# 04-POWERV2_1.net
KiCad netlist of a schematic drawn in Altium Designer
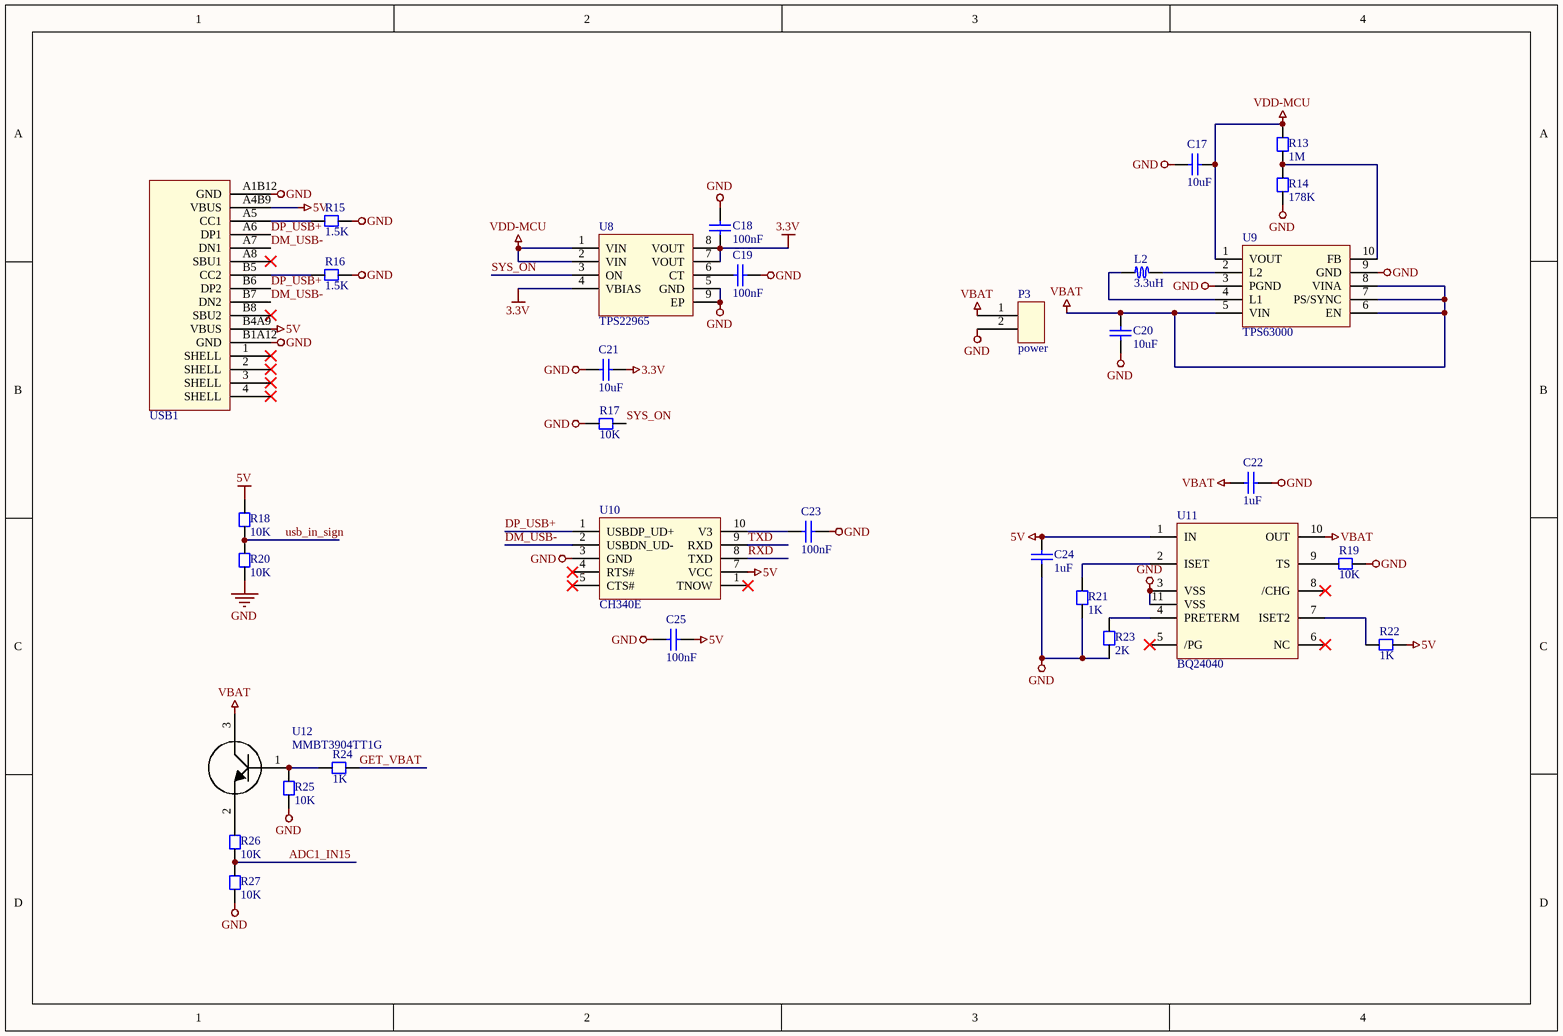
[diagram p0: 04-POWERV2.1.SchDoc]

(export (version "E")
  (design (tool "Eeschema 10.0.6"))
  (components
    (comp (ref "C17")
      (value "10uF")
      (footprint "CC1005-0402")
      (description "贴片电容")
      (libsource (lib "tianxiaohua_Schlib") (part "Chip capacitor"))
    )
    (comp (ref "C18")
      (value "100nF")
      (footprint "CC1005-0402")
      (description "贴片电容")
      (libsource (lib "tianxiaohua_Schlib") (part "Chip capacitor"))
    )
    (comp (ref "C19")
      (value "100nF")
      (footprint "CC1005-0402")
      (description "贴片电容")
      (libsource (lib "tianxiaohua_Schlib") (part "Chip capacitor"))
    )
    (comp (ref "C20")
      (value "10uF")
      (footprint "CC1005-0402")
      (description "贴片电容")
      (libsource (lib "tianxiaohua_Schlib") (part "Chip capacitor"))
    )
    (comp (ref "C21")
      (value "10uF")
      (footprint "CC1005-0402")
      (description "贴片电容")
      (libsource (lib "tianxiaohua_Schlib") (part "Chip capacitor"))
    )
    (comp (ref "C22")
      (value "1uF")
      (footprint "CC1005-0402")
      (description "贴片电容")
      (libsource (lib "tianxiaohua_Schlib") (part "Chip capacitor"))
    )
    (comp (ref "C23")
      (value "100nF")
      (footprint "CC1005-0402")
      (description "贴片电容")
      (libsource (lib "tianxiaohua_Schlib") (part "Chip capacitor"))
    )
    (comp (ref "C24")
      (value "1uF")
      (footprint "CC1005-0402")
      (description "贴片电容")
      (libsource (lib "tianxiaohua_Schlib") (part "Chip capacitor"))
    )
    (comp (ref "C25")
      (value "100nF")
      (footprint "CC1005-0402")
      (description "贴片电容")
      (libsource (lib "tianxiaohua_Schlib") (part "Chip capacitor"))
    )
    (comp (ref "L2")
      (value "3.3uH")
      (footprint "Inductor-0805")
      (description "贴片电感")
      (libsource (lib "tianxiaohua_Schlib") (part "Chip inductor"))
    )
    (comp (ref "P3")
      (value "power")
      (footprint "POWER-3.7V")
      (libsource (lib "tianxiaohua_Schlib") (part "power"))
    )
    (comp (ref "R13")
      (value "1M")
      (footprint "CR1005-0402")
      (description "贴片电阻")
      (libsource (lib "") (part "Chip resistor_1"))
    )
    (comp (ref "R14")
      (value "178K")
      (footprint "CR1005-0402")
      (description "贴片电阻")
      (libsource (lib "") (part "Chip resistor_3"))
    )
    (comp (ref "R15")
      (value "1.5K")
      (footprint "CR1005-0402")
      (description "贴片电阻")
      (libsource (lib "") (part "Chip resistor_2"))
    )
    (comp (ref "R16")
      (value "1.5K")
      (footprint "CR1005-0402")
      (description "贴片电阻")
      (libsource (lib "") (part "Chip resistor_2"))
    )
    (comp (ref "R17")
      (value "10K")
      (footprint "CR1005-0402")
      (description "贴片电阻")
      (libsource (lib "") (part "Chip resistor_2"))
    )
    (comp (ref "R18")
      (value "10K")
      (footprint "CR1005-0402")
      (description "贴片电阻")
      (libsource (lib "") (part "Chip resistor_1"))
    )
    (comp (ref "R19")
      (value "10K")
      (footprint "CR1005-0402")
      (description "贴片电阻")
      (libsource (lib "tianxiaohua_Schlib") (part "Chip resistor"))
    )
    (comp (ref "R20")
      (value "10K")
      (footprint "CR1005-0402")
      (description "贴片电阻")
      (libsource (lib "") (part "Chip resistor_1"))
    )
    (comp (ref "R21")
      (value "1K")
      (footprint "CR1005-0402")
      (description "贴片电阻")
      (libsource (lib "") (part "Chip resistor_1"))
    )
    (comp (ref "R22")
      (value "1K")
      (footprint "CR1005-0402")
      (description "贴片电阻")
      (libsource (lib "tianxiaohua_Schlib") (part "Chip resistor"))
    )
    (comp (ref "R23")
      (value "2K")
      (footprint "CR1005-0402")
      (description "贴片电阻")
      (libsource (lib "") (part "Chip resistor_1"))
    )
    (comp (ref "R24")
      (value "1K")
      (footprint "CR1005-0402")
      (description "贴片电阻")
      (libsource (lib "tianxiaohua_Schlib") (part "Chip resistor"))
    )
    (comp (ref "R25")
      (value "10K")
      (footprint "CR1005-0402")
      (description "贴片电阻")
      (libsource (lib "") (part "Chip resistor_1"))
    )
    (comp (ref "R26")
      (value "10K")
      (footprint "CR1005-0402")
      (description "贴片电阻")
      (libsource (lib "") (part "Chip resistor_1"))
    )
    (comp (ref "R27")
      (value "10K")
      (footprint "CR1005-0402")
      (description "贴片电阻")
      (libsource (lib "") (part "Chip resistor_1"))
    )
    (comp (ref "U8")
      (value "TPS22965")
      (footprint "UDFN-8")
      (description "DFN-8 功率开关芯片 TPS22965DSGR")
      (libsource (lib "tianxiaohua_Schlib") (part "TPS22965"))
    )
    (comp (ref "U9")
      (value "TPS63000")
      (footprint "SON10")
      (description "宽电压电源转换芯片输出3.3V输入1V至6V")
      (libsource (lib "tianxiaohua_Schlib") (part "TPS63000"))
    )
    (comp (ref "U10")
      (value "CH340E")
      (footprint "MSOP-10")
      (description "usd转串口芯片 MSOP10封装")
      (libsource (lib "tianxiaohua_Schlib") (part "CH340E"))
    )
    (comp (ref "U11")
      (value "BQ24040")
      (footprint "WSON-10_L2.0-W2.0-P0.40-BL-EP")
      (description "1A 具有自动启动功能的单输入，单节锂离子和锂聚合物电池充电\r\n器")
      (libsource (lib "tianxiaohua_Schlib") (part "BQ24041"))
    )
    (comp (ref "U12")
      (value "MMBT3904TT1G")
      (footprint "SOT-416")
      (description "NPN 电流 - 集电极（Ic）（最大值）：200mA 电压 - 集射极击穿（最大值）：40V SOT-23-3")
      (libsource (lib "tianxiaohua_Schlib") (part "MMBT3904TT1G"))
    )
    (comp (ref "USB1")
      (value "Tpye-c 16P")
      (footprint "TYPE-C 16P")
      (description "16P 封装的TYPE -c接口 4固定插脚 双向")
      (libsource (lib "tianxiaohua_Schlib") (part "Tpye-c 16P"))
    )
  )
  (nets
    (net (code "1") (name "/ADC1_IN15") (class "Default")
      (node (ref "R26") (pin "2") (pinfunction "2_2") (pintype "passive"))
      (node (ref "R27") (pin "1") (pinfunction "1_1") (pintype "passive"))
    )
    (net (code "2") (name "/DM_USB-") (class "Default")
      (node (ref "U10") (pin "2") (pinfunction "USBDN_UD-_2") (pintype "passive"))
      (node (ref "USB1") (pin "A7") (pinfunction "DN1_A7") (pintype "power_in"))
      (node (ref "USB1") (pin "B7") (pinfunction "DN2_B7") (pintype "power_in"))
    )
    (net (code "3") (name "/DP_USB+") (class "Default")
      (node (ref "U10") (pin "1") (pinfunction "USBDP_UD+_1") (pintype "passive"))
      (node (ref "USB1") (pin "A6") (pinfunction "DP1_A6") (pintype "power_in"))
      (node (ref "USB1") (pin "B6") (pinfunction "DP2_B6") (pintype "power_in"))
    )
    (net (code "4") (name "/GET_VBAT") (class "Default")
      (node (ref "R24") (pin "2") (pinfunction "2_2") (pintype "passive"))
    )
    (net (code "5") (name "/RXD") (class "Default")
      (node (ref "U10") (pin "8") (pinfunction "TXD_8") (pintype "passive"))
    )
    (net (code "6") (name "/SYS_ON") (class "Default")
      (node (ref "R17") (pin "1") (pinfunction "1_1") (pintype "passive"))
      (node (ref "U8") (pin "3") (pinfunction "ON_3") (pintype "passive"))
    )
    (net (code "7") (name "/TXD") (class "Default")
      (node (ref "U10") (pin "9") (pinfunction "RXD_9") (pintype "passive"))
    )
    (net (code "8") (name "/usb_in_sign") (class "Default")
      (node (ref "R18") (pin "2") (pinfunction "2_2") (pintype "passive"))
      (node (ref "R20") (pin "1") (pinfunction "1_1") (pintype "passive"))
    )
    (net (code "9") (name "3.3V") (class "Default")
      (node (ref "C18") (pin "1") (pinfunction "1_1") (pintype "passive"))
      (node (ref "C21") (pin "2") (pinfunction "2_2") (pintype "passive"))
      (node (ref "U8") (pin "4") (pinfunction "VBIAS_4") (pintype "passive"))
      (node (ref "U8") (pin "7") (pinfunction "VOUT_7") (pintype "passive"))
      (node (ref "U8") (pin "8") (pinfunction "VOUT_8") (pintype "passive"))
    )
    (net (code "10") (name "5V") (class "Default")
      (node (ref "C24") (pin "1") (pinfunction "1_1") (pintype "passive"))
      (node (ref "C25") (pin "2") (pinfunction "2_2") (pintype "passive"))
      (node (ref "R18") (pin "1") (pinfunction "1_1") (pintype "passive"))
      (node (ref "R22") (pin "2") (pinfunction "2_2") (pintype "passive"))
      (node (ref "U10") (pin "7") (pinfunction "VCC_7") (pintype "passive"))
      (node (ref "U11") (pin "1") (pinfunction "IN_1") (pintype "passive"))
      (node (ref "USB1") (pin "A4B9") (pinfunction "VBUS_A4B9") (pintype "power_in"))
      (node (ref "USB1") (pin "B4A9") (pinfunction "VBUS_B4A9") (pintype "power_in"))
    )
    (net (code "11") (name "GND") (class "Default")
      (node (ref "C17") (pin "1") (pinfunction "1_1") (pintype "passive"))
      (node (ref "C18") (pin "2") (pinfunction "2_2") (pintype "passive"))
      (node (ref "C19") (pin "1") (pinfunction "1_1") (pintype "passive"))
      (node (ref "C20") (pin "1") (pinfunction "1_1") (pintype "passive"))
      (node (ref "C21") (pin "1") (pinfunction "1_1") (pintype "passive"))
      (node (ref "C22") (pin "1") (pinfunction "1_1") (pintype "passive"))
      (node (ref "C23") (pin "2") (pinfunction "2_2") (pintype "passive"))
      (node (ref "C24") (pin "2") (pinfunction "2_2") (pintype "passive"))
      (node (ref "C25") (pin "1") (pinfunction "1_1") (pintype "passive"))
      (node (ref "P3") (pin "2") (pinfunction "2_2") (pintype "passive"))
      (node (ref "R14") (pin "1") (pinfunction "1_1") (pintype "passive"))
      (node (ref "R15") (pin "1") (pinfunction "1_1") (pintype "passive"))
      (node (ref "R16") (pin "1") (pinfunction "1_1") (pintype "passive"))
      (node (ref "R17") (pin "2") (pinfunction "2_2") (pintype "passive"))
      (node (ref "R19") (pin "2") (pinfunction "2_2") (pintype "passive"))
      (node (ref "R20") (pin "2") (pinfunction "2_2") (pintype "passive"))
      (node (ref "R21") (pin "2") (pinfunction "2_2") (pintype "passive"))
      (node (ref "R23") (pin "2") (pinfunction "2_2") (pintype "passive"))
      (node (ref "R25") (pin "2") (pinfunction "2_2") (pintype "passive"))
      (node (ref "R27") (pin "2") (pinfunction "2_2") (pintype "passive"))
      (node (ref "U10") (pin "3") (pinfunction "GND_3") (pintype "passive"))
      (node (ref "U11") (pin "11") (pinfunction "VSS_11") (pintype "passive"))
      (node (ref "U11") (pin "3") (pinfunction "VSS_3") (pintype "passive"))
      (node (ref "U8") (pin "5") (pinfunction "GND_5") (pintype "passive"))
      (node (ref "U8") (pin "9") (pinfunction "EP_9") (pintype "passive"))
      (node (ref "U9") (pin "3") (pinfunction "PGND_3") (pintype "passive"))
      (node (ref "U9") (pin "9") (pinfunction "GND_9") (pintype "passive"))
      (node (ref "USB1") (pin "A1B12") (pinfunction "GND_A1B12") (pintype "power_in"))
      (node (ref "USB1") (pin "B1A12") (pinfunction "GND_B1A12") (pintype "power_in"))
    )
    (net (code "12") (name "Net-(R24-Pad1)") (class "Default")
      (node (ref "R24") (pin "1") (pinfunction "1_1") (pintype "passive"))
      (node (ref "R25") (pin "1") (pinfunction "1_1") (pintype "passive"))
      (node (ref "U12") (pin "1") (pinfunction "1_1") (pintype "passive"))
    )
    (net (code "13") (name "Net-(R26-Pad1)") (class "Default")
      (node (ref "R26") (pin "1") (pinfunction "1_1") (pintype "passive"))
      (node (ref "U12") (pin "2") (pinfunction "2_2") (pintype "passive"))
    )
    (net (code "14") (name "Net-(U8-CT)") (class "Default")
      (node (ref "C19") (pin "2") (pinfunction "2_2") (pintype "passive"))
      (node (ref "U8") (pin "6") (pinfunction "CT_6") (pintype "passive"))
    )
    (net (code "15") (name "Net-(U9-FB)") (class "Default")
      (node (ref "R13") (pin "2") (pinfunction "2_2") (pintype "passive"))
      (node (ref "R14") (pin "2") (pinfunction "2_2") (pintype "passive"))
      (node (ref "U9") (pin "10") (pinfunction "FB_10") (pintype "passive"))
    )
    (net (code "16") (name "Net-(U9-L1)") (class "Default")
      (node (ref "L2") (pin "1") (pinfunction "1_1") (pintype "passive"))
      (node (ref "U9") (pin "4") (pinfunction "L1_4") (pintype "passive"))
    )
    (net (code "17") (name "Net-(U9-L2)") (class "Default")
      (node (ref "L2") (pin "2") (pinfunction "2_2") (pintype "passive"))
      (node (ref "U9") (pin "2") (pinfunction "L2_2") (pintype "passive"))
    )
    (net (code "18") (name "Net-(U10-V3)") (class "Default")
      (node (ref "C23") (pin "1") (pinfunction "1_1") (pintype "passive"))
      (node (ref "U10") (pin "10") (pinfunction "V3_10") (pintype "passive"))
    )
    (net (code "19") (name "Net-(U11-ISET)") (class "Default")
      (node (ref "R21") (pin "1") (pinfunction "1_1") (pintype "passive"))
      (node (ref "U11") (pin "2") (pinfunction "ISET_2") (pintype "passive"))
    )
    (net (code "20") (name "Net-(U11-ISET2)") (class "Default")
      (node (ref "R22") (pin "1") (pinfunction "1_1") (pintype "passive"))
      (node (ref "U11") (pin "7") (pinfunction "ISET2_7") (pintype "passive"))
    )
    (net (code "21") (name "Net-(U11-PRETERM)") (class "Default")
      (node (ref "R23") (pin "1") (pinfunction "1_1") (pintype "passive"))
      (node (ref "U11") (pin "4") (pinfunction "PRETERM_4") (pintype "passive"))
    )
    (net (code "22") (name "Net-(U11-TS)") (class "Default")
      (node (ref "R19") (pin "1") (pinfunction "1_1") (pintype "passive"))
      (node (ref "U11") (pin "9") (pinfunction "TS_9") (pintype "passive"))
    )
    (net (code "23") (name "Net-(USB1-CC1)") (class "Default")
      (node (ref "R15") (pin "2") (pinfunction "2_2") (pintype "passive"))
      (node (ref "USB1") (pin "A5") (pinfunction "CC1_A5") (pintype "power_in"))
    )
    (net (code "24") (name "Net-(USB1-CC2)") (class "Default")
      (node (ref "R16") (pin "2") (pinfunction "2_2") (pintype "passive"))
      (node (ref "USB1") (pin "B5") (pinfunction "CC2_B5") (pintype "power_in"))
    )
    (net (code "25") (name "VBAT") (class "Default")
      (node (ref "C20") (pin "2") (pinfunction "2_2") (pintype "passive"))
      (node (ref "C22") (pin "2") (pinfunction "2_2") (pintype "passive"))
      (node (ref "P3") (pin "1") (pinfunction "1_1") (pintype "passive"))
      (node (ref "U11") (pin "10") (pinfunction "OUT_10") (pintype "passive"))
      (node (ref "U12") (pin "3") (pinfunction "3_3") (pintype "passive"))
      (node (ref "U9") (pin "5") (pinfunction "VIN_5") (pintype "passive"))
      (node (ref "U9") (pin "6") (pinfunction "EN_6") (pintype "passive"))
      (node (ref "U9") (pin "7") (pinfunction "PS/SYNC_7") (pintype "passive"))
      (node (ref "U9") (pin "8") (pinfunction "VINA_8") (pintype "passive"))
    )
    (net (code "26") (name "VDD-MCU") (class "Default")
      (node (ref "C17") (pin "2") (pinfunction "2_2") (pintype "passive"))
      (node (ref "R13") (pin "1") (pinfunction "1_1") (pintype "passive"))
      (node (ref "U8") (pin "1") (pinfunction "VIN_1") (pintype "passive"))
      (node (ref "U8") (pin "2") (pinfunction "VIN_2") (pintype "passive"))
      (node (ref "U9") (pin "1") (pinfunction "VOUT_1") (pintype "passive"))
    )
    (net (code "27") (name "unconnected-(U10-CTS#-Pad5)") (class "Default")
      (node (ref "U10") (pin "5") (pinfunction "CTS#_5") (pintype "passive+no_connect"))
    )
    (net (code "28") (name "unconnected-(U10-RTS#-Pad4)") (class "Default")
      (node (ref "U10") (pin "4") (pinfunction "RTS#_4") (pintype "passive+no_connect"))
    )
    (net (code "29") (name "unconnected-(U10-TNOW-Pad1)") (class "Default")
      (node (ref "U10") (pin "1") (pinfunction "TNOW_1") (pintype "passive+no_connect"))
    )
    (net (code "30") (name "unconnected-(U11-NC-Pad6)") (class "Default")
      (node (ref "U11") (pin "6") (pinfunction "NC_6") (pintype "passive+no_connect"))
    )
    (net (code "31") (name "unconnected-(U11-{slash}CHG-Pad8)") (class "Default")
      (node (ref "U11") (pin "8") (pinfunction "/CHG_8") (pintype "passive+no_connect"))
    )
    (net (code "32") (name "unconnected-(U11-{slash}PG-Pad5)") (class "Default")
      (node (ref "U11") (pin "5") (pinfunction "/PG_5") (pintype "passive+no_connect"))
    )
    (net (code "33") (name "unconnected-(USB1-SBU1-PadA8)") (class "Default")
      (node (ref "USB1") (pin "A8") (pinfunction "SBU1_A8") (pintype "power_in+no_connect"))
    )
    (net (code "34") (name "unconnected-(USB1-SBU2-PadB8)") (class "Default")
      (node (ref "USB1") (pin "B8") (pinfunction "SBU2_B8") (pintype "power_in+no_connect"))
    )
    (net (code "35") (name "unconnected-(USB1-SHELL-Pad1)") (class "Default")
      (node (ref "USB1") (pin "1") (pinfunction "SHELL_1") (pintype "power_in+no_connect"))
    )
    (net (code "36") (name "unconnected-(USB1-SHELL-Pad2)") (class "Default")
      (node (ref "USB1") (pin "2") (pinfunction "SHELL_2") (pintype "power_in+no_connect"))
    )
    (net (code "37") (name "unconnected-(USB1-SHELL-Pad3)") (class "Default")
      (node (ref "USB1") (pin "3") (pinfunction "SHELL_3") (pintype "power_in+no_connect"))
    )
    (net (code "38") (name "unconnected-(USB1-SHELL-Pad4)") (class "Default")
      (node (ref "USB1") (pin "4") (pinfunction "SHELL_4") (pintype "power_in+no_connect"))
    )
  )
)
